# OBPeripheral.net
KiCad netlist of a schematic drawn in Altium Designer
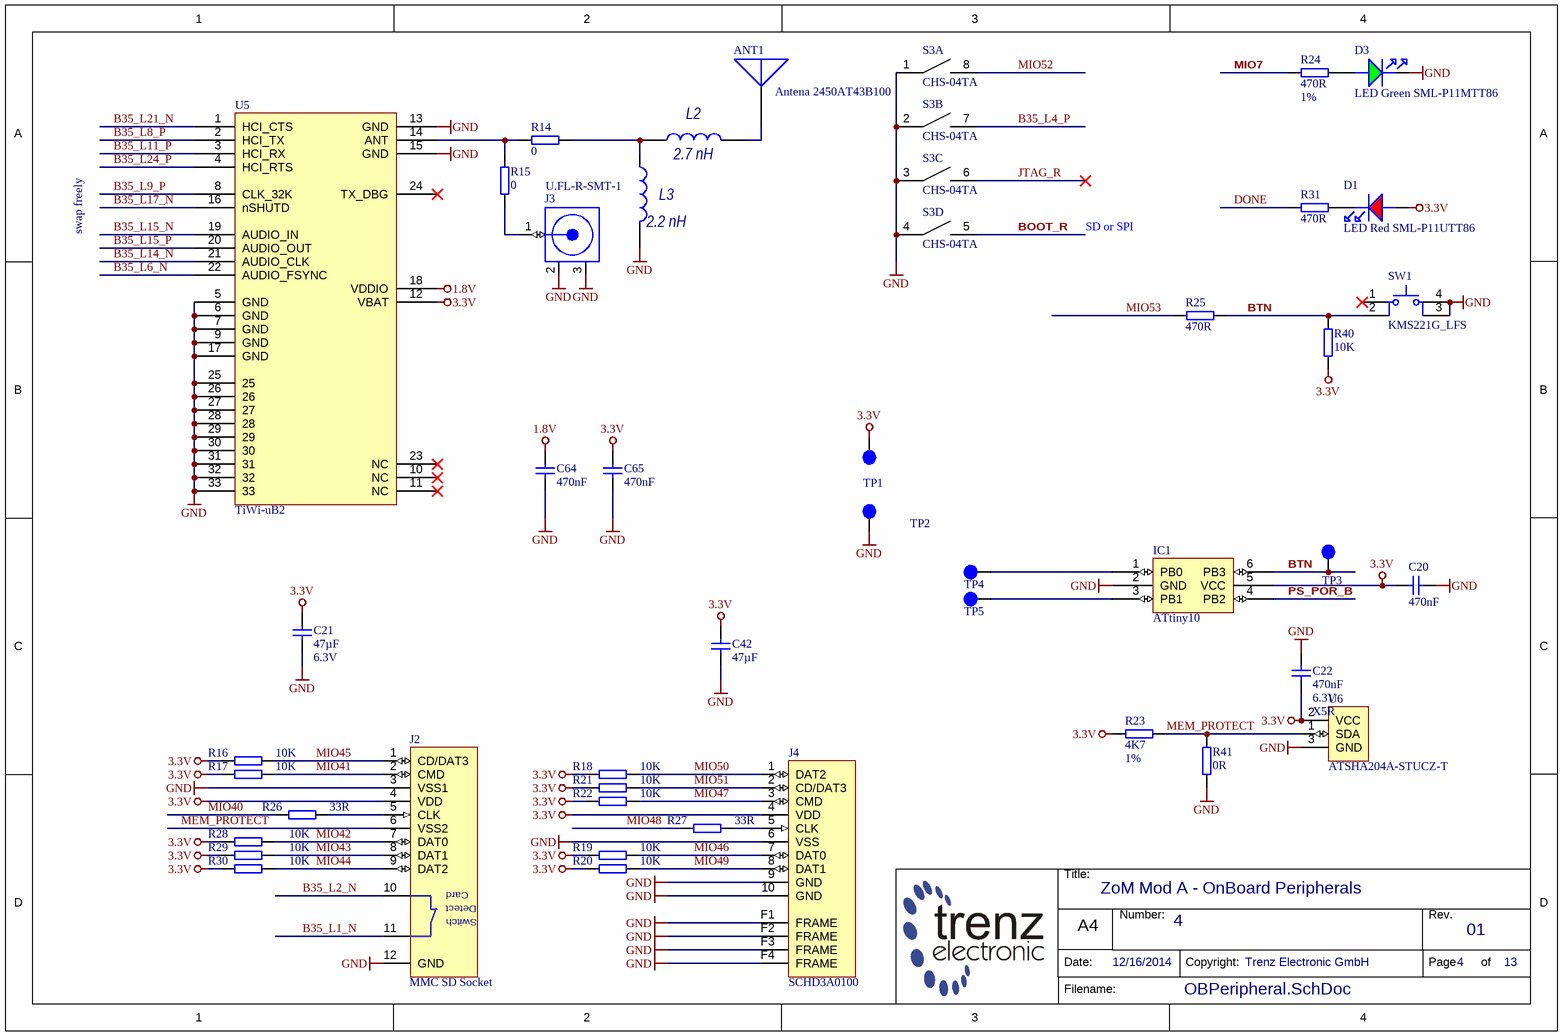
[diagram p0: OBPeripheral.SchDoc]

(export (version "E")
  (design (tool "Eeschema 10.0.6"))
  (components
    (comp (ref "ANT1")
      (value "Antena 2450AT43B100")
      (footprint "Antena 2450AT43B100")
      (libsource (lib "TiWi-uB2") (part "Antena 2450AT43B100"))
    )
    (comp (ref "C20")
      (value "470nF")
      (footprint "CAPC0603X33N")
      (description "KON 470nF X5R 6.3V SMD")
      (fields (field (name "VOLTAGE") "6.3V") (field (name "TOLERANCE") "20%"))
      (libsource (lib "TE") (part "CAP-NP"))
    )
    (comp (ref "C21")
      (value "47µF")
      (footprint "CAPC3216X180N")
      (description "KON 47µF 6.3V  X5R SMD 20%")
      (fields (field (name "VOLTAGE") "6.3V") (field (name "TOLERANCE") "20%"))
      (libsource (lib "TE") (part "CAP-NP"))
    )
    (comp (ref "C22")
      (value "470nF")
      (footprint "CAPC0603X33N")
      (description "KON 470nF X5R 6.3V SMD")
      (fields
        (field (name "VOLTAGE") "6.3V")
        (field (name "TECHNOLOGY") "X5R")
        (field (name "TOLERANCE") "20%")
      )
      (libsource (lib "TE") (part "CAP-NP"))
    )
    (comp (ref "C42")
      (value "47µF")
      (footprint "CAPC3216X180N")
      (description "KON 47µF 6.3V  X5R SMD 20%")
      (fields (field (name "VOLTAGE") "6.3V") (field (name "TOLERANCE") "20%"))
      (libsource (lib "TE") (part "CAP-NP"))
    )
    (comp (ref "C64")
      (value "470nF")
      (footprint "CAPC0603X33N")
      (description "KON 470nF X5R 6.3V SMD")
      (fields (field (name "VOLTAGE") "6.3V") (field (name "TOLERANCE") "20%"))
      (libsource (lib "TE") (part "CAP-NP"))
    )
    (comp (ref "C65")
      (value "470nF")
      (footprint "CAPC0603X33N")
      (description "KON 470nF X5R 6.3V SMD")
      (fields (field (name "VOLTAGE") "6.3V") (field (name "TOLERANCE") "20%"))
      (libsource (lib "TE") (part "CAP-NP"))
    )
    (comp (ref "D1")
      (value "LED Red SML-P11UTT86")
      (footprint "LEDC1006X25N_RED")
      (description "LED Rot SML-P11UTT86 SMD")
      (libsource (lib "TE") (part "LED_ROT"))
    )
    (comp (ref "D3")
      (value "LED Green SML-P11MTT86")
      (footprint "LEDC1006X25N_GREEN")
      (description "LED Grün SML-P11MTT86 SMD")
      (libsource (lib "TE") (part "LED_GRUEN"))
    )
    (comp (ref "IC1")
      (value "ATtiny10")
      (footprint "SOT23-6")
      (fields (field (name "Comment") "Atmel AVR ATtiny10"))
      (libsource (lib "trioflex-cadlib") (part "ATtiny10"))
    )
    (comp (ref "J2")
      (value "MMC SD Socket")
      (footprint "104C-TAA0-R")
      (description "MCC SD Socket")
      (libsource (lib "TE") (part "104C-TAA0-R"))
    )
    (comp (ref "J3")
      (value "U.FL-R-SMT-1")
      (footprint "U.FL-R-SMT-1")
      (description "Hirose Ultra Small Coaxial Connector")
      (libsource (lib "TE") (part "UFL"))
    )
    (comp (ref "J4")
      (value "SCHD3A0100")
      (footprint "SCHD3A0100")
      (description "microSD Card (Header Type) SCHD Series")
      (libsource (lib "TE") (part "SCHD3A0100"))
    )
    (comp (ref "L2")
      (value "IND-Ferrite")
      (footprint "RESC1005X40R")
      (description "Ferrite Inductor")
      (fields (field (name "US_VISIBLESCH") "2.7 nH"))
      (libsource (lib "TiWi-uB2") (part "IND-Ferrite"))
    )
    (comp (ref "L3")
      (value "IND-Ferrite")
      (footprint "RESC1005X40R")
      (description "Ferrite Inductor")
      (fields (field (name "US_VISIBLESCH") "2.2 nH"))
      (libsource (lib "TiWi-uB2") (part "IND-Ferrite"))
    )
    (comp (ref "R14")
      (value "0")
      (footprint "RESC0603X26N")
      (description "WID SMD 0")
      (libsource (lib "TE") (part "RES"))
    )
    (comp (ref "R15")
      (value "0")
      (footprint "RESC0603X26N")
      (description "WID SMD 0")
      (libsource (lib "TE") (part "RES"))
    )
    (comp (ref "R16")
      (value "10K")
      (footprint "RESC0603X26N")
      (description "WID SMD 10K 1% 0,05W")
      (fields (field (name "TOLERANCE") "1%"))
      (libsource (lib "TE") (part "RES"))
    )
    (comp (ref "R17")
      (value "10K")
      (footprint "RESC0603X26N")
      (description "WID SMD 10K 1% 0,05W")
      (fields (field (name "TOLERANCE") "1%"))
      (libsource (lib "TE") (part "RES"))
    )
    (comp (ref "R18")
      (value "10K")
      (footprint "RESC0603X26N")
      (description "WID SMD 10K 1% 0,05W")
      (fields (field (name "TOLERANCE") "1%"))
      (libsource (lib "TE") (part "RES"))
    )
    (comp (ref "R19")
      (value "10K")
      (footprint "RESC0603X26N")
      (description "WID SMD 10K 1% 0,05W")
      (fields (field (name "TOLERANCE") "1%"))
      (libsource (lib "TE") (part "RES"))
    )
    (comp (ref "R20")
      (value "10K")
      (footprint "RESC0603X26N")
      (description "WID SMD 10K 1% 0,05W")
      (fields (field (name "TOLERANCE") "1%"))
      (libsource (lib "TE") (part "RES"))
    )
    (comp (ref "R21")
      (value "10K")
      (footprint "RESC0603X26N")
      (description "WID SMD 10K 1% 0,05W")
      (fields (field (name "TOLERANCE") "1%"))
      (libsource (lib "TE") (part "RES"))
    )
    (comp (ref "R22")
      (value "10K")
      (footprint "RESC0603X26N")
      (description "WID SMD 10K 1% 0,05W")
      (fields (field (name "TOLERANCE") "1%"))
      (libsource (lib "TE") (part "RES"))
    )
    (comp (ref "R23")
      (value "4K7")
      (footprint "RESC0603X26N")
      (description "WID SMD 4K7 1% 0,05W")
      (fields (field (name "TOLERANCE") "1%"))
      (libsource (lib "TE") (part "RES"))
    )
    (comp (ref "R24")
      (value "470R")
      (footprint "RESC1005X40N")
      (description "WID SMD 470R 1% 0,063W")
      (fields (field (name "TOLERANCE") "1%"))
      (libsource (lib "TE") (part "RES"))
    )
    (comp (ref "R25")
      (value "470R")
      (footprint "RESC1005X40N")
      (description "WID SMD 470R 1% 0,063W")
      (fields (field (name "TOLERANCE") "1%"))
      (libsource (lib "TE") (part "RES"))
    )
    (comp (ref "R26")
      (value "33R")
      (footprint "RESC0603X26N")
      (description "WID SMD 33R 1% 0,05W")
      (libsource (lib "TE") (part "RES"))
    )
    (comp (ref "R27")
      (value "33R")
      (footprint "RESC0603X26N")
      (description "WID SMD 33R 1% 0,05W")
      (libsource (lib "TE") (part "RES"))
    )
    (comp (ref "R28")
      (value "10K")
      (footprint "RESC0603X26N")
      (description "WID SMD 10K 1% 0,05W")
      (fields (field (name "TOLERANCE") "1%"))
      (libsource (lib "TE") (part "RES"))
    )
    (comp (ref "R29")
      (value "10K")
      (footprint "RESC0603X26N")
      (description "WID SMD 10K 1% 0,05W")
      (fields (field (name "TOLERANCE") "1%"))
      (libsource (lib "TE") (part "RES"))
    )
    (comp (ref "R30")
      (value "10K")
      (footprint "RESC0603X26N")
      (description "WID SMD 10K 1% 0,05W")
      (fields (field (name "TOLERANCE") "1%"))
      (libsource (lib "TE") (part "RES"))
    )
    (comp (ref "R31")
      (value "470R")
      (footprint "RESC1005X40N")
      (description "WID SMD 470R 1% 0,063W")
      (fields (field (name "TOLERANCE") "1%"))
      (libsource (lib "TE") (part "RES"))
    )
    (comp (ref "R40")
      (value "10K")
      (footprint "RESC0603X26N")
      (description "WID SMD 10K 1% 0,05W")
      (fields (field (name "TOLERANCE") "1%"))
      (libsource (lib "TE") (part "RES"))
    )
    (comp (ref "R41")
      (value "0R")
      (footprint "RESC1005X40N")
      (description "WID SMD 0R")
      (libsource (lib "TE") (part "RES"))
    )
    (comp (ref "S3")
      (value "CHS-04TA")
      (footprint "CHS-04TA")
      (description "DIP Schalter 4 fach 1,27mm SMD")
      (libsource (lib "TE") (part "CHS-04TA"))
    )
    (comp (ref "SW1")
      (value "KMS221G_LFS")
      (footprint "KMS221G_LFS")
      (description "4pin button")
      (libsource (lib "trioflex-cadlib") (part "BUT-4P"))
    )
    (comp (ref "TP1")
      (value "TP")
      (footprint "TP-SMD-2mm")
      (description "Testpoint")
      (libsource (lib "trioflex-cadlib") (part "TP"))
    )
    (comp (ref "TP2")
      (value "TP")
      (footprint "TP-SMD-2mm")
      (description "Testpoint")
      (libsource (lib "trioflex-cadlib") (part "TP"))
    )
    (comp (ref "TP3")
      (value "TP")
      (footprint "TP-SMD-2mm")
      (description "Testpoint")
      (libsource (lib "trioflex-cadlib") (part "TP"))
    )
    (comp (ref "TP4")
      (value "TP")
      (footprint "TP-SMD-2mm")
      (description "Testpoint")
      (libsource (lib "trioflex-cadlib") (part "TP"))
    )
    (comp (ref "TP5")
      (value "TP")
      (footprint "TP-SMD-2mm")
      (description "Testpoint")
      (libsource (lib "trioflex-cadlib") (part "TP"))
    )
    (comp (ref "U5") (value "TiWi-uB2") (footprint "TiWi-uB2") (libsource (lib "TiWi-uB2") (part "TiWi-uB2")))
    (comp (ref "U6")
      (value "ATSHA204A-STUCZ-T")
      (footprint "SOT95P237X112-3N")
      (libsource (lib "TE") (part "ATSHA204-TSU-T"))
    )
  )
  (nets
    (net (code "1") (name "/B35_L1_N") (class "Default")
      (node (ref "J2") (pin "11") (pinfunction "11_11") (pintype "passive"))
    )
    (net (code "2") (name "/B35_L2_N") (class "Default")
      (node (ref "J2") (pin "10") (pinfunction "10_10") (pintype "passive"))
    )
    (net (code "3") (name "/B35_L4_P") (class "Default")
      (node (ref "S3") (pin "7") (pinfunction "7_7") (pintype "passive"))
    )
    (net (code "4") (name "/B35_L6_N") (class "Default")
      (node (ref "U5") (pin "22") (pinfunction "AUDIO_FSYNC_22") (pintype "passive"))
    )
    (net (code "5") (name "/B35_L8_P") (class "Default")
      (node (ref "U5") (pin "2") (pinfunction "HCI_TX_2") (pintype "passive"))
    )
    (net (code "6") (name "/B35_L9_P") (class "Default")
      (node (ref "U5") (pin "8") (pinfunction "CLK_32K_8") (pintype "passive"))
    )
    (net (code "7") (name "/B35_L11_P") (class "Default")
      (node (ref "U5") (pin "3") (pinfunction "HCI_RX_3") (pintype "passive"))
    )
    (net (code "8") (name "/B35_L14_N") (class "Default")
      (node (ref "U5") (pin "21") (pinfunction "AUDIO_CLK_21") (pintype "passive"))
    )
    (net (code "9") (name "/B35_L15_N") (class "Default")
      (node (ref "U5") (pin "19") (pinfunction "AUDIO_IN_19") (pintype "passive"))
    )
    (net (code "10") (name "/B35_L15_P") (class "Default")
      (node (ref "U5") (pin "20") (pinfunction "AUDIO_OUT_20") (pintype "passive"))
    )
    (net (code "11") (name "/B35_L17_N") (class "Default")
      (node (ref "U5") (pin "16") (pinfunction "nSHUTD_16") (pintype "passive"))
    )
    (net (code "12") (name "/B35_L21_N") (class "Default")
      (node (ref "U5") (pin "1") (pinfunction "HCI_CTS_1") (pintype "passive"))
    )
    (net (code "13") (name "/B35_L24_P") (class "Default")
      (node (ref "U5") (pin "4") (pinfunction "HCI_RTS_4") (pintype "passive"))
    )
    (net (code "14") (name "/BOOT_R") (class "Default")
      (node (ref "S3") (pin "5") (pinfunction "5_5") (pintype "passive"))
    )
    (net (code "15") (name "/BTN") (class "Default")
      (node (ref "IC1") (pin "6") (pinfunction "PB3_6") (pintype "bidirectional"))
      (node (ref "R25") (pin "1") (pinfunction "1_1") (pintype "passive"))
      (node (ref "R40") (pin "1") (pinfunction "1_1") (pintype "passive"))
      (node (ref "SW1") (pin "2") (pinfunction "2_2") (pintype "passive"))
      (node (ref "TP3") (pin "1") (pinfunction "1_1") (pintype "passive"))
    )
    (net (code "16") (name "/DONE") (class "Default")
      (node (ref "R31") (pin "2") (pinfunction "2_2") (pintype "passive"))
    )
    (net (code "17") (name "/JTAG_R") (class "Default")
      (node (ref "S3") (pin "6") (pinfunction "6_6") (pintype "passive+no_connect"))
    )
    (net (code "18") (name "/MEM_PROTECT") (class "Default")
      (node (ref "J2") (pin "6") (pinfunction "VSS2_6") (pintype "power_in"))
      (node (ref "R23") (pin "1") (pinfunction "1_1") (pintype "passive"))
      (node (ref "R41") (pin "1") (pinfunction "1_1") (pintype "passive"))
      (node (ref "U6") (pin "1") (pinfunction "SDA_1") (pintype "bidirectional"))
    )
    (net (code "19") (name "/MIO7") (class "Default")
      (node (ref "R24") (pin "2") (pinfunction "2_2") (pintype "passive"))
    )
    (net (code "20") (name "/MIO40") (class "Default")
      (node (ref "R26") (pin "1") (pinfunction "1_1") (pintype "passive"))
    )
    (net (code "21") (name "/MIO41") (class "Default")
      (node (ref "J2") (pin "2") (pinfunction "CMD_2") (pintype "bidirectional"))
      (node (ref "R17") (pin "2") (pinfunction "2_2") (pintype "passive"))
    )
    (net (code "22") (name "/MIO42") (class "Default")
      (node (ref "J2") (pin "7") (pinfunction "DAT0_7") (pintype "bidirectional"))
      (node (ref "R28") (pin "2") (pinfunction "2_2") (pintype "passive"))
    )
    (net (code "23") (name "/MIO43") (class "Default")
      (node (ref "J2") (pin "8") (pinfunction "DAT1_8") (pintype "bidirectional"))
      (node (ref "R29") (pin "2") (pinfunction "2_2") (pintype "passive"))
    )
    (net (code "24") (name "/MIO44") (class "Default")
      (node (ref "J2") (pin "9") (pinfunction "DAT2_9") (pintype "bidirectional"))
      (node (ref "R30") (pin "2") (pinfunction "2_2") (pintype "passive"))
    )
    (net (code "25") (name "/MIO45") (class "Default")
      (node (ref "J2") (pin "1") (pinfunction "CD/DAT3_1") (pintype "bidirectional"))
      (node (ref "R16") (pin "2") (pinfunction "2_2") (pintype "passive"))
    )
    (net (code "26") (name "/MIO46") (class "Default")
      (node (ref "J4") (pin "7") (pinfunction "DAT0_7") (pintype "bidirectional"))
      (node (ref "R19") (pin "2") (pinfunction "2_2") (pintype "passive"))
    )
    (net (code "27") (name "/MIO47") (class "Default")
      (node (ref "J4") (pin "3") (pinfunction "CMD_3") (pintype "bidirectional"))
      (node (ref "R22") (pin "2") (pinfunction "2_2") (pintype "passive"))
    )
    (net (code "28") (name "/MIO48") (class "Default")
      (node (ref "R27") (pin "1") (pinfunction "1_1") (pintype "passive"))
    )
    (net (code "29") (name "/MIO49") (class "Default")
      (node (ref "J4") (pin "8") (pinfunction "DAT1_8") (pintype "bidirectional"))
      (node (ref "R20") (pin "2") (pinfunction "2_2") (pintype "passive"))
    )
    (net (code "30") (name "/MIO50") (class "Default")
      (node (ref "J4") (pin "1") (pinfunction "DAT2_1") (pintype "bidirectional"))
      (node (ref "R18") (pin "2") (pinfunction "2_2") (pintype "passive"))
    )
    (net (code "31") (name "/MIO51") (class "Default")
      (node (ref "J4") (pin "2") (pinfunction "CD/DAT3_2") (pintype "bidirectional"))
      (node (ref "R21") (pin "2") (pinfunction "2_2") (pintype "passive"))
    )
    (net (code "32") (name "/MIO52") (class "Default")
      (node (ref "S3") (pin "8") (pinfunction "8_8") (pintype "passive"))
    )
    (net (code "33") (name "/MIO53") (class "Default")
      (node (ref "R25") (pin "2") (pinfunction "2_2") (pintype "passive"))
    )
    (net (code "34") (name "/PS_POR_B") (class "Default")
      (node (ref "IC1") (pin "4") (pinfunction "PB2_4") (pintype "bidirectional"))
    )
    (net (code "35") (name "1.8V") (class "Default")
      (node (ref "C64") (pin "1") (pinfunction "1_1") (pintype "passive"))
      (node (ref "U5") (pin "18") (pinfunction "VDDIO_18") (pintype "passive"))
    )
    (net (code "36") (name "3.3V") (class "Default")
      (node (ref "C20") (pin "1") (pinfunction "1_1") (pintype "passive"))
      (node (ref "C21") (pin "1") (pinfunction "1_1") (pintype "passive"))
      (node (ref "C22") (pin "2") (pinfunction "2_2") (pintype "passive"))
      (node (ref "C42") (pin "1") (pinfunction "1_1") (pintype "passive"))
      (node (ref "C65") (pin "1") (pinfunction "1_1") (pintype "passive"))
      (node (ref "D1") (pin "A") (pinfunction "A_A") (pintype "passive"))
      (node (ref "IC1") (pin "5") (pinfunction "VCC_5") (pintype "power_in"))
      (node (ref "J2") (pin "4") (pinfunction "VDD_4") (pintype "power_in"))
      (node (ref "J4") (pin "4") (pinfunction "VDD_4") (pintype "power_in"))
      (node (ref "R16") (pin "1") (pinfunction "1_1") (pintype "passive"))
      (node (ref "R17") (pin "1") (pinfunction "1_1") (pintype "passive"))
      (node (ref "R18") (pin "1") (pinfunction "1_1") (pintype "passive"))
      (node (ref "R19") (pin "1") (pinfunction "1_1") (pintype "passive"))
      (node (ref "R20") (pin "1") (pinfunction "1_1") (pintype "passive"))
      (node (ref "R21") (pin "1") (pinfunction "1_1") (pintype "passive"))
      (node (ref "R22") (pin "1") (pinfunction "1_1") (pintype "passive"))
      (node (ref "R23") (pin "2") (pinfunction "2_2") (pintype "passive"))
      (node (ref "R28") (pin "1") (pinfunction "1_1") (pintype "passive"))
      (node (ref "R29") (pin "1") (pinfunction "1_1") (pintype "passive"))
      (node (ref "R30") (pin "1") (pinfunction "1_1") (pintype "passive"))
      (node (ref "R40") (pin "2") (pinfunction "2_2") (pintype "passive"))
      (node (ref "TP1") (pin "1") (pinfunction "1_1") (pintype "passive"))
      (node (ref "U5") (pin "12") (pinfunction "VBAT_12") (pintype "passive"))
      (node (ref "U6") (pin "2") (pinfunction "VCC_2") (pintype "power_in"))
    )
    (net (code "37") (name "GND") (class "Default")
      (node (ref "C20") (pin "2") (pinfunction "2_2") (pintype "passive"))
      (node (ref "C21") (pin "2") (pinfunction "2_2") (pintype "passive"))
      (node (ref "C22") (pin "1") (pinfunction "1_1") (pintype "passive"))
      (node (ref "C42") (pin "2") (pinfunction "2_2") (pintype "passive"))
      (node (ref "C64") (pin "2") (pinfunction "2_2") (pintype "passive"))
      (node (ref "C65") (pin "2") (pinfunction "2_2") (pintype "passive"))
      (node (ref "D3") (pin "K") (pinfunction "K_K") (pintype "passive"))
      (node (ref "IC1") (pin "2") (pinfunction "GND_2") (pintype "power_in"))
      (node (ref "J2") (pin "12") (pinfunction "GND_12") (pintype "power_in"))
      (node (ref "J2") (pin "3") (pinfunction "VSS1_3") (pintype "power_in"))
      (node (ref "J3") (pin "2") (pinfunction "GND_2") (pintype "power_in"))
      (node (ref "J3") (pin "3") (pinfunction "GND_3") (pintype "power_in"))
      (node (ref "J4") (pin "10") (pinfunction "GND_10") (pintype "power_in"))
      (node (ref "J4") (pin "6") (pinfunction "VSS_6") (pintype "power_in"))
      (node (ref "J4") (pin "9") (pinfunction "GND_9") (pintype "power_in"))
      (node (ref "J4") (pin "F1") (pinfunction "FRAME_F1") (pintype "passive"))
      (node (ref "J4") (pin "F2") (pinfunction "FRAME_F2") (pintype "passive"))
      (node (ref "J4") (pin "F3") (pinfunction "FRAME_F3") (pintype "passive"))
      (node (ref "J4") (pin "F4") (pinfunction "FRAME_F4") (pintype "passive"))
      (node (ref "L3") (pin "2") (pinfunction "2_2") (pintype "passive"))
      (node (ref "R41") (pin "2") (pinfunction "2_2") (pintype "passive"))
      (node (ref "S3") (pin "1") (pinfunction "1_1") (pintype "passive"))
      (node (ref "S3") (pin "2") (pinfunction "2_2") (pintype "passive"))
      (node (ref "S3") (pin "3") (pinfunction "3_3") (pintype "passive"))
      (node (ref "S3") (pin "4") (pinfunction "4_4") (pintype "passive"))
      (node (ref "SW1") (pin "3") (pinfunction "3_3") (pintype "passive"))
      (node (ref "SW1") (pin "4") (pinfunction "4_4") (pintype "passive"))
      (node (ref "TP2") (pin "1") (pinfunction "1_1") (pintype "passive"))
      (node (ref "U5") (pin "13") (pinfunction "GND_13") (pintype "passive"))
      (node (ref "U5") (pin "15") (pinfunction "GND_15") (pintype "passive"))
      (node (ref "U5") (pin "17") (pinfunction "GND_17") (pintype "passive"))
      (node (ref "U5") (pin "25") (pinfunction "25_25") (pintype "passive"))
      (node (ref "U5") (pin "26") (pinfunction "26_26") (pintype "passive"))
      (node (ref "U5") (pin "27") (pinfunction "27_27") (pintype "passive"))
      (node (ref "U5") (pin "28") (pinfunction "28_28") (pintype "passive"))
      (node (ref "U5") (pin "29") (pinfunction "29_29") (pintype "passive"))
      (node (ref "U5") (pin "30") (pinfunction "30_30") (pintype "passive"))
      (node (ref "U5") (pin "31") (pinfunction "31_31") (pintype "passive"))
      (node (ref "U5") (pin "32") (pinfunction "32_32") (pintype "passive"))
      (node (ref "U5") (pin "33") (pinfunction "33_33") (pintype "passive"))
      (node (ref "U5") (pin "5") (pinfunction "GND_5") (pintype "passive"))
      (node (ref "U5") (pin "6") (pinfunction "GND_6") (pintype "passive"))
      (node (ref "U5") (pin "7") (pinfunction "GND_7") (pintype "passive"))
      (node (ref "U5") (pin "9") (pinfunction "GND_9") (pintype "passive"))
      (node (ref "U6") (pin "3") (pinfunction "GND_3") (pintype "power_in"))
    )
    (net (code "38") (name "Net-(ANT1-Feed_Point)") (class "Default")
      (node (ref "ANT1") (pin "1") (pinfunction "Feed_Point_1") (pintype "passive"))
      (node (ref "L2") (pin "2") (pinfunction "2_2") (pintype "passive"))
    )
    (net (code "39") (name "Net-(D1-PadK)") (class "Default")
      (node (ref "D1") (pin "K") (pinfunction "K_K") (pintype "passive"))
      (node (ref "R31") (pin "1") (pinfunction "1_1") (pintype "passive"))
    )
    (net (code "40") (name "Net-(D3-PadA)") (class "Default")
      (node (ref "D3") (pin "A") (pinfunction "A_A") (pintype "passive"))
      (node (ref "R24") (pin "1") (pinfunction "1_1") (pintype "passive"))
    )
    (net (code "41") (name "Net-(IC1-PB0)") (class "Default")
      (node (ref "IC1") (pin "1") (pinfunction "PB0_1") (pintype "bidirectional"))
      (node (ref "TP4") (pin "1") (pinfunction "1_1") (pintype "passive"))
    )
    (net (code "42") (name "Net-(IC1-PB1)") (class "Default")
      (node (ref "IC1") (pin "3") (pinfunction "PB1_3") (pintype "bidirectional"))
      (node (ref "TP5") (pin "1") (pinfunction "1_1") (pintype "passive"))
    )
    (net (code "43") (name "Net-(J2-CLK)") (class "Default")
      (node (ref "J2") (pin "5") (pinfunction "CLK_5") (pintype "input"))
      (node (ref "R26") (pin "2") (pinfunction "2_2") (pintype "passive"))
    )
    (net (code "44") (name "Net-(J3-Signal)") (class "Default")
      (node (ref "J3") (pin "1") (pinfunction "Signal_1") (pintype "bidirectional"))
      (node (ref "R15") (pin "1") (pinfunction "1_1") (pintype "passive"))
    )
    (net (code "45") (name "Net-(J4-CLK)") (class "Default")
      (node (ref "J4") (pin "5") (pinfunction "CLK_5") (pintype "input"))
      (node (ref "R27") (pin "2") (pinfunction "2_2") (pintype "passive"))
    )
    (net (code "46") (name "Net-(L2-Pad1)") (class "Default")
      (node (ref "L2") (pin "1") (pinfunction "1_1") (pintype "passive"))
      (node (ref "L3") (pin "1") (pinfunction "1_1") (pintype "passive"))
      (node (ref "R14") (pin "2") (pinfunction "2_2") (pintype "passive"))
    )
    (net (code "47") (name "Net-(U5-ANT)") (class "Default")
      (node (ref "R14") (pin "1") (pinfunction "1_1") (pintype "passive"))
      (node (ref "R15") (pin "2") (pinfunction "2_2") (pintype "passive"))
      (node (ref "U5") (pin "14") (pinfunction "ANT_14") (pintype "passive"))
    )
    (net (code "48") (name "unconnected-(SW1-Pad1)") (class "Default")
      (node (ref "SW1") (pin "1") (pinfunction "1_1") (pintype "passive+no_connect"))
    )
    (net (code "49") (name "unconnected-(U5-NC-Pad10)") (class "Default")
      (node (ref "U5") (pin "10") (pinfunction "NC_10") (pintype "passive+no_connect"))
    )
    (net (code "50") (name "unconnected-(U5-NC-Pad11)") (class "Default")
      (node (ref "U5") (pin "11") (pinfunction "NC_11") (pintype "passive+no_connect"))
    )
    (net (code "51") (name "unconnected-(U5-NC-Pad23)") (class "Default")
      (node (ref "U5") (pin "23") (pinfunction "NC_23") (pintype "passive+no_connect"))
    )
    (net (code "52") (name "unconnected-(U5-TX_DBG-Pad24)") (class "Default")
      (node (ref "U5") (pin "24") (pinfunction "TX_DBG_24") (pintype "passive+no_connect"))
    )
  )
)
